# processing.net
KiCad netlist of a schematic drawn in Altium Designer
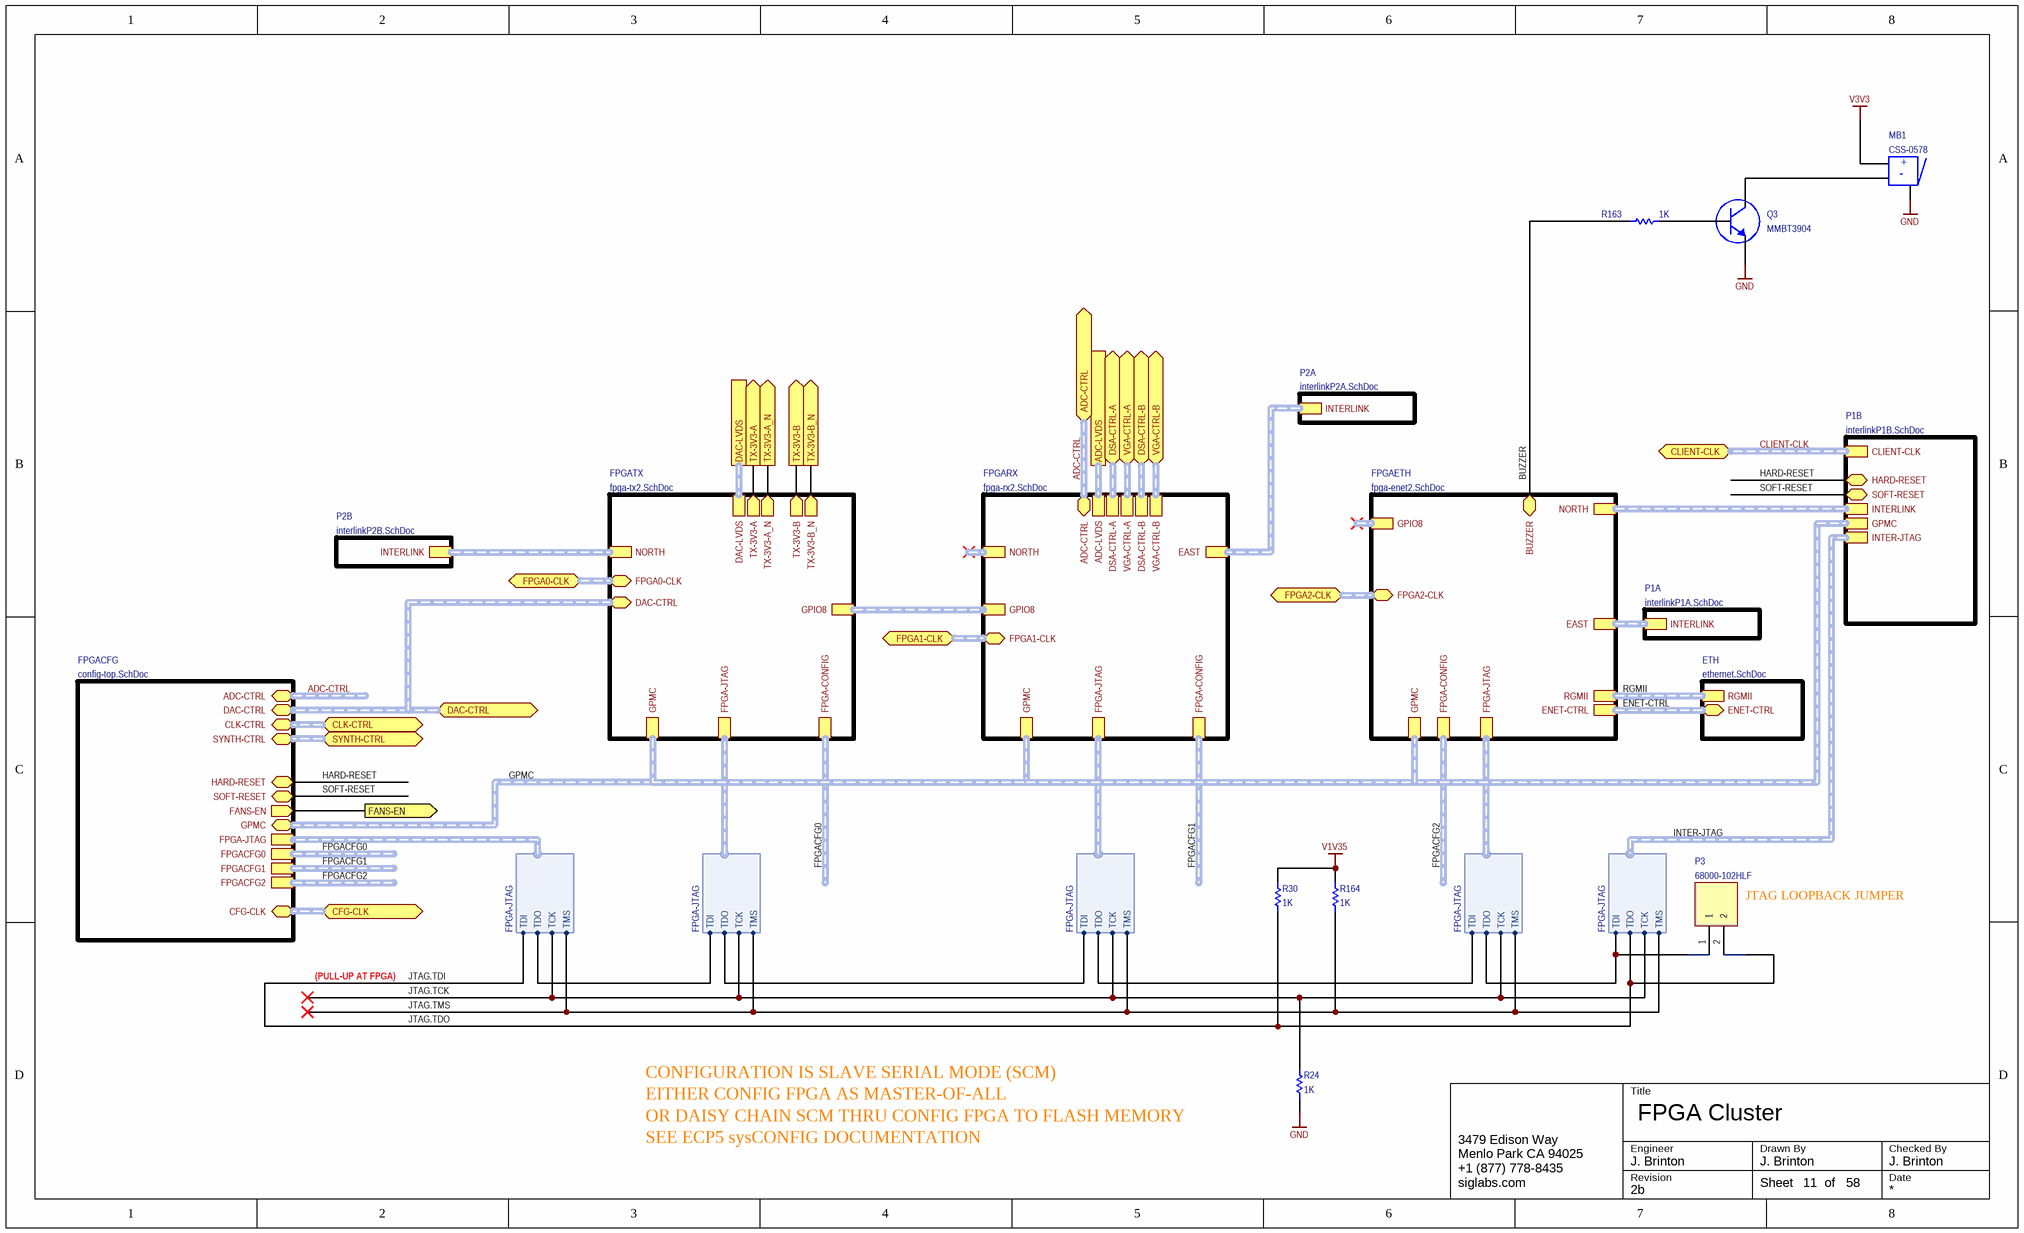
[diagram p0: processing.SchDoc]

(export (version "E")
  (design (tool "Eeschema 10.0.6"))
  (components
    (comp (ref "MB1")
      (value "CSS-0578")
      (footprint "CSS-0578")
      (description "Magnetic Buzzer")
      (fields (field (name "MANUFACTURER") "CUI, Inc."))
      (libsource (lib "generic") (part "CSS-0578"))
    )
    (comp (ref "P3")
      (value "68000-102HLF")
      (footprint "68000-102HLF")
      (description "Connector; Header; 2 Position; 0.1\" Pitch")
      (fields (field (name "MANUFACTURER") "FCI"))
      (libsource (lib "fci") (part "68000-102HLF"))
    )
    (comp (ref "Q3")
      (value "MMBT3904")
      (footprint "SOT23")
      (description "NPN General Purpose Amplifier")
      (fields (field (name "MANUFACTURER") "Fairchild Semiconductor"))
      (libsource (lib "fairchild") (part "2N3904"))
    )
    (comp (ref "R24")
      (value "1K")
      (footprint "generic:0402")
      (description "Thick Film Resistor 1k ±1% 0402")
      (fields (field (name "MANUFACTURER") "Yageo") (field (name "TOLERANCE") "±1%"))
      (libsource (lib "Graviton") (part "RES 0402"))
    )
    (comp (ref "R30")
      (value "1K")
      (footprint "generic:0402")
      (description "Thick Film Resistor 1k ±1% 0402")
      (fields (field (name "MANUFACTURER") "Yageo") (field (name "TOLERANCE") "±1%"))
      (libsource (lib "generic") (part "RES 0402"))
    )
    (comp (ref "R163")
      (value "1K")
      (footprint "generic:0402")
      (description "Thick Film Resistor 1k ±1% 0402")
      (fields (field (name "MANUFACTURER") "Yageo") (field (name "TOLERANCE") "±1%"))
      (libsource (lib "Graviton") (part "RES 0402"))
    )
    (comp (ref "R164")
      (value "1K")
      (footprint "generic:0402")
      (description "Thick Film Resistor 1k ±1% 0402")
      (fields (field (name "MANUFACTURER") "Yageo") (field (name "TOLERANCE") "±1%"))
      (libsource (lib "generic") (part "RES 0402"))
    )
  )
  (nets
    (net (code "25") (name "/BUZZER") (class "Default")
      (node (ref "R163") (pin "2") (pinfunction "2_2") (pintype "passive"))
    )
    (net (code "44") (name "/JTAG.TCK") (class "Default")
      (node (ref "R24") (pin "1") (pinfunction "1_1") (pintype "passive+no_connect"))
    )
    (net (code "45") (name "/JTAG.TDI") (class "Default")
      (node (ref "P3") (pin "2") (pinfunction "2_2") (pintype "passive"))
      (node (ref "R30") (pin "1") (pinfunction "1_1") (pintype "passive"))
    )
    (net (code "46") (name "/JTAG.TMS") (class "Default")
      (node (ref "R164") (pin "1") (pinfunction "1_1") (pintype "passive+no_connect"))
    )
    (net (code "65") (name "GND") (class "Default")
      (node (ref "MB1") (pin "3") (pinfunction "TAB_3") (pintype "passive"))
      (node (ref "Q3") (pin "2") (pinfunction "E_2") (pintype "passive"))
      (node (ref "R24") (pin "2") (pinfunction "2_2") (pintype "passive"))
    )
    (net (code "66") (name "Net-(MB1-NEG)") (class "Default")
      (node (ref "MB1") (pin "2") (pinfunction "NEG_2") (pintype "passive"))
      (node (ref "Q3") (pin "3") (pinfunction "C_3") (pintype "passive"))
    )
    (net (code "67") (name "Net-(Q3-B)") (class "Default")
      (node (ref "Q3") (pin "1") (pinfunction "B_1") (pintype "passive"))
      (node (ref "R163") (pin "1") (pinfunction "1_1") (pintype "passive"))
    )
    (net (code "68") (name "V1V35") (class "Default")
      (node (ref "R164") (pin "2") (pinfunction "2_2") (pintype "passive"))
      (node (ref "R30") (pin "2") (pinfunction "2_2") (pintype "passive"))
    )
    (net (code "69") (name "V3V3") (class "Default")
      (node (ref "MB1") (pin "1") (pinfunction "POS_1") (pintype "passive"))
    )
    (net (code "70") (name "unconnected-(P3-Pad1)") (class "Default")
      (node (ref "P3") (pin "1") (pinfunction "1_1") (pintype "passive"))
    )
  )
)
